# 8_dc_dc_5V_5A_Radio.net
KiCad netlist of a schematic drawn in Altium Designer
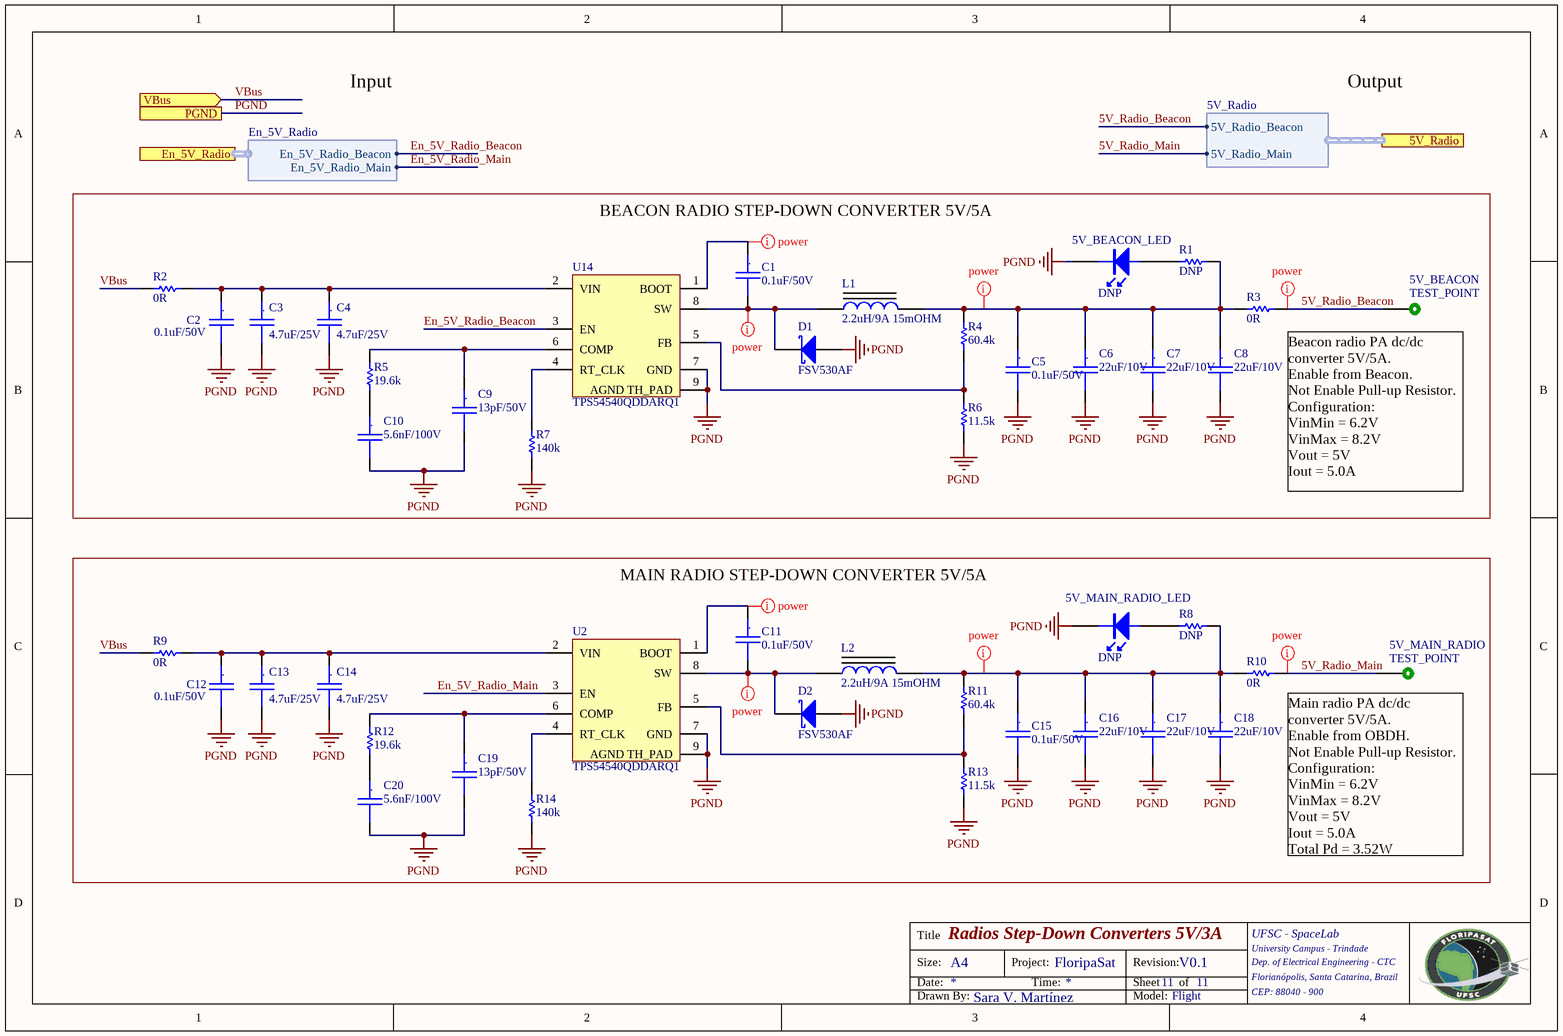
[diagram p0: 8_dc_dc_5V_5A_Radio.SchDoc]

(export (version "E")
  (design (tool "Eeschema 10.0.6"))
  (components
    (comp (ref "5V_BEACON")
      (value "TEST_POINT")
      (footprint "TEST_POINT")
      (description "Test point")
      (libsource (lib "Floripasat_lib") (part "TEST_POINT"))
    )
    (comp (ref "5V_BEACON_LED")
      (value "DNP")
      (footprint "0603-LED")
      (description "SMD Green LED")
      (fields (field (name "PARTNUMBER") "150060VS75000"))
      (libsource (lib "FloripaSatSchlib") (part "LED/G_0603"))
    )
    (comp (ref "5V_MAIN_RADIO")
      (value "TEST_POINT")
      (footprint "TEST_POINT")
      (description "Test point")
      (libsource (lib "Floripasat_lib") (part "TEST_POINT"))
    )
    (comp (ref "5V_MAIN_RADIO_LED")
      (value "DNP")
      (footprint "0603-LED")
      (description "SMD Green LED")
      (fields (field (name "PARTNUMBER") "150060VS75000"))
      (libsource (lib "FloripaSatSchlib") (part "LED/G_0603"))
    )
    (comp (ref "C1")
      (value "0.1uF/50V")
      (footprint "CC0805")
      (description "CAP CER 0.1UF 50V 10% X7R 0805")
      (fields (field (name "PARTNUMBER") "CC0805KRX7R9BB104"))
      (libsource (lib "PCB_Project_FlightModel_EPS") (part "Cap_Cer_X7R_0.1uF_50V_0805"))
    )
    (comp (ref "C2")
      (value "0.1uF/50V")
      (footprint "CC0805")
      (description "CAP CER 0.1UF 50V 10% X7R 0805")
      (fields (field (name "PARTNUMBER") "CC0805KRX7R9BB104"))
      (libsource (lib "PCB_Project_FlightModel_EPS") (part "Cap_Cer_X7R_0.1uF_50V_0805"))
    )
    (comp (ref "C3")
      (value "4.7uF/25V")
      (footprint "CC0805")
      (description "CAP CER 4.7uF 25V 10% X7R 0805")
      (fields (field (name "PARTNUMBER") "CC0805KKX7R8BB475"))
      (libsource (lib "PCB_Project_FlightModel_EPS") (part "Cap_Cer_X7R_4.7uF_25V_0805"))
    )
    (comp (ref "C4")
      (value "4.7uF/25V")
      (footprint "CC0805")
      (description "CAP CER 4.7uF 25V 10% X7R 0805")
      (fields (field (name "PARTNUMBER") "CC0805KKX7R8BB475"))
      (libsource (lib "PCB_Project_FlightModel_EPS") (part "Cap_Cer_X7R_4.7uF_25V_0805"))
    )
    (comp (ref "C5")
      (value "0.1uF/50V")
      (footprint "CC0805")
      (description "CAP CER 0.1UF 50V 10% X7R 0805")
      (fields (field (name "PARTNUMBER") "CC0805KRX7R9BB104"))
      (libsource (lib "PCB_Project_FlightModel_EPS") (part "Cap_Cer_X7R_0.1uF_50V_0805"))
    )
    (comp (ref "C6")
      (value "22uF/10V")
      (footprint "CC1206")
      (description "CAP CER 22uF 10V 10% X7R 1206")
      (fields (field (name "PARTNUMBER") "GRM31CR71A226KE15L"))
      (libsource (lib "PCB_Project_FlightModel_EPS") (part "Cap_Cer_X7R_22uF_10V_1206"))
    )
    (comp (ref "C7")
      (value "22uF/10V")
      (footprint "CC1206")
      (description "CAP CER 22uF 10V 10% X7R 1206")
      (fields (field (name "PARTNUMBER") "GRM31CR71A226KE15L"))
      (libsource (lib "PCB_Project_FlightModel_EPS") (part "Cap_Cer_X7R_22uF_10V_1206"))
    )
    (comp (ref "C8")
      (value "22uF/10V")
      (footprint "CC1206")
      (description "CAP CER 22uF 10V 10% X7R 1206")
      (fields (field (name "PARTNUMBER") "GRM31CR71A226KE15L"))
      (libsource (lib "PCB_Project_FlightModel_EPS") (part "Cap_Cer_X7R_22uF_10V_1206"))
    )
    (comp (ref "C9")
      (value "13pF/50V")
      (footprint "CC0603")
      (description "CAP CER 13PF 50V 0603 NP0")
      (fields (field (name "PARTNUMBER") "C0603C130J5GAC7867"))
      (libsource (lib "PCB_Project_FlightModel_EPS") (part "Cap_Cer_C0G_13pF_50V_0603"))
    )
    (comp (ref "C10")
      (value "5.6nF/100V")
      (footprint "CC0603")
      (description "CAP CER 5.6nF 100V 0603")
      (fields (field (name "PARTNUMBER") "C1608C0G2A562J080AE"))
      (libsource (lib "FloripaSatSchlib") (part "Cap_Cer_C0G_5.6nF_100V_0603"))
    )
    (comp (ref "C11")
      (value "0.1uF/50V")
      (footprint "CC0805")
      (description "CAP CER 0.1UF 50V 10% X7R 0805")
      (fields (field (name "PARTNUMBER") "CC0805KRX7R9BB104"))
      (libsource (lib "PCB_Project_FlightModel_EPS") (part "Cap_Cer_X7R_0.1uF_50V_0805"))
    )
    (comp (ref "C12")
      (value "0.1uF/50V")
      (footprint "CC0805")
      (description "CAP CER 0.1UF 50V 10% X7R 0805")
      (fields (field (name "PARTNUMBER") "CC0805KRX7R9BB104"))
      (libsource (lib "PCB_Project_FlightModel_EPS") (part "Cap_Cer_X7R_0.1uF_50V_0805"))
    )
    (comp (ref "C13")
      (value "4.7uF/25V")
      (footprint "CC0805")
      (description "CAP CER 4.7uF 25V 10% X7R 0805")
      (fields (field (name "PARTNUMBER") "CC0805KKX7R8BB475"))
      (libsource (lib "PCB_Project_FlightModel_EPS") (part "Cap_Cer_X7R_4.7uF_25V_0805"))
    )
    (comp (ref "C14")
      (value "4.7uF/25V")
      (footprint "CC0805")
      (description "CAP CER 4.7uF 25V 10% X7R 0805")
      (fields (field (name "PARTNUMBER") "CC0805KKX7R8BB475"))
      (libsource (lib "PCB_Project_FlightModel_EPS") (part "Cap_Cer_X7R_4.7uF_25V_0805"))
    )
    (comp (ref "C15")
      (value "0.1uF/50V")
      (footprint "CC0805")
      (description "CAP CER 0.1UF 50V 10% X7R 0805")
      (fields (field (name "PARTNUMBER") "CC0805KRX7R9BB104"))
      (libsource (lib "PCB_Project_FlightModel_EPS") (part "Cap_Cer_X7R_0.1uF_50V_0805"))
    )
    (comp (ref "C16")
      (value "22uF/10V")
      (footprint "CC1206")
      (description "CAP CER 22uF 10V 10% X7R 1206")
      (fields (field (name "PARTNUMBER") "GRM31CR71A226KE15L"))
      (libsource (lib "PCB_Project_FlightModel_EPS") (part "Cap_Cer_X7R_22uF_10V_1206"))
    )
    (comp (ref "C17")
      (value "22uF/10V")
      (footprint "CC1206")
      (description "CAP CER 22uF 10V 10% X7R 1206")
      (fields (field (name "PARTNUMBER") "GRM31CR71A226KE15L"))
      (libsource (lib "PCB_Project_FlightModel_EPS") (part "Cap_Cer_X7R_22uF_10V_1206"))
    )
    (comp (ref "C18")
      (value "22uF/10V")
      (footprint "CC1206")
      (description "CAP CER 22uF 10V 10% X7R 1206")
      (fields (field (name "PARTNUMBER") "GRM31CR71A226KE15L"))
      (libsource (lib "PCB_Project_FlightModel_EPS") (part "Cap_Cer_X7R_22uF_10V_1206"))
    )
    (comp (ref "C19")
      (value "13pF/50V")
      (footprint "CC0603")
      (description "CAP CER 13PF 50V 0603 NP0")
      (fields (field (name "PARTNUMBER") "C0603C130J5GAC7867"))
      (libsource (lib "PCB_Project_FlightModel_EPS") (part "Cap_Cer_C0G_13pF_50V_0603"))
    )
    (comp (ref "C20")
      (value "5.6nF/100V")
      (footprint "CC0603")
      (description "CAP CER 5.6nF 100V 0603")
      (fields (field (name "PARTNUMBER") "C1608C0G2A562J080AE"))
      (libsource (lib "FloripaSatSchlib") (part "Cap_Cer_C0G_5.6nF_100V_0603"))
    )
    (comp (ref "D1")
      (value "FSV530AF")
      (footprint "DO-214AC")
      (description "DIODE SCHOTTKY 30V 5A DO-214AA")
      (libsource (lib "FloripaSatSchlib") (part "DIODE_SCHOTTKY_30V_5A_RB080L-30TE25"))
    )
    (comp (ref "D2")
      (value "FSV530AF")
      (footprint "DO-214AC")
      (description "DIODE SCHOTTKY 30V 5A DO-214AA")
      (libsource (lib "FloripaSatSchlib") (part "DIODE_SCHOTTKY_30V_5A_RB080L-30TE25"))
    )
    (comp (ref "L1")
      (value "2.2uH/9A 15mOHM")
      (footprint "Ind_SRP6540")
      (description "INDUCTOR 2.2UH 9A SMD")
      (fields (field (name "PARTNUMBER") "SRP6540-2R2M"))
      (libsource (lib "FloripaSatSchlib") (part "IND_POWER_2.2uH_9A_15mR"))
    )
    (comp (ref "L2")
      (value "2.2uH/9A 15mOHM")
      (footprint "Ind_SRP6540")
      (description "INDUCTOR 2.2UH 9A SMD")
      (fields (field (name "PARTNUMBER") "SRP6540-2R2M"))
      (libsource (lib "FloripaSatSchlib") (part "IND_POWER_2.2uH_9A_15mR"))
    )
    (comp (ref "R1")
      (value "DNP")
      (footprint "0603")
      (description "RES 1.0K OHM 1/8W 1% 0603")
      (fields (field (name "PARTNUMBER") "MCT06030C1001FP500"))
      (libsource (lib "FloripaSatSchlib") (part "R1.0k_1%_1/8W_0603"))
    )
    (comp (ref "R2")
      (value "0R")
      (footprint "1206")
      (description "RES 0.0 OHM 3/4W JUMP 1206")
      (fields (field (name "PARTNUMBER") "HCJ1206ZT0R00"))
      (libsource (lib "PCB_Project_FlightModel_EPS") (part "R0R_JUMPER_3/4W_1206"))
    )
    (comp (ref "R3")
      (value "0R")
      (footprint "1206")
      (description "RES 0.0 OHM 3/4W JUMP 1206")
      (fields (field (name "PARTNUMBER") "HCJ1206ZT0R00"))
      (libsource (lib "PCB_Project_FlightModel_EPS") (part "R0R_JUMPER_3/4W_1206"))
    )
    (comp (ref "R4")
      (value "60.4k")
      (footprint "0805")
      (description "RES 60.4k OHM 1/8W 1% 0805")
      (fields (field (name "PARTNUMBER") "ERJ-6ENF6042V"))
      (libsource (lib "FloripaSatSchlib") (part "R60.4k_1%_1/8W_0805"))
    )
    (comp (ref "R5")
      (value "19.6k")
      (footprint "0603")
      (description "RES 19.6k OHM 1/10W 1% 0603")
      (fields (field (name "PARTNUMBER") "ERJ-3EKF1962V"))
      (libsource (lib "FloripaSatSchlib") (part "R19.6k_1%_1/10W_0603"))
    )
    (comp (ref "R6")
      (value "11.5k")
      (footprint "0805")
      (description "RES 11.5k OHM 1/8W 1% 0805")
      (fields (field (name "PARTNUMBER") "AC0805FR-0711K5L"))
      (libsource (lib "FloripaSatSchlib") (part "R11.5k_1%_1/8W_0805"))
    )
    (comp (ref "R7")
      (value "140k")
      (footprint "0603")
      (description "RES 140k OHM 1/5W 1% 0603")
      (fields (field (name "PARTNUMBER") "ERJ-P03F1403V"))
      (libsource (lib "FloripaSatSchlib") (part "R140k_1%_1/5W_0603"))
    )
    (comp (ref "R8")
      (value "DNP")
      (footprint "0603")
      (description "RES 1.0K OHM 1/8W 1% 0603")
      (fields (field (name "PARTNUMBER") "MCT06030C1001FP500"))
      (libsource (lib "FloripaSatSchlib") (part "R1.0k_1%_1/8W_0603"))
    )
    (comp (ref "R9")
      (value "0R")
      (footprint "1206")
      (description "RES 0.0 OHM 3/4W JUMP 1206")
      (fields (field (name "PARTNUMBER") "HCJ1206ZT0R00"))
      (libsource (lib "PCB_Project_FlightModel_EPS") (part "R0R_JUMPER_3/4W_1206"))
    )
    (comp (ref "R10")
      (value "0R")
      (footprint "1206")
      (description "RES 0.0 OHM 3/4W JUMP 1206")
      (fields (field (name "PARTNUMBER") "HCJ1206ZT0R00"))
      (libsource (lib "PCB_Project_FlightModel_EPS") (part "R0R_JUMPER_3/4W_1206"))
    )
    (comp (ref "R11")
      (value "60.4k")
      (footprint "0805")
      (description "RES 60.4k OHM 1/8W 1% 0805")
      (fields (field (name "PARTNUMBER") "ERJ-6ENF6042V"))
      (libsource (lib "FloripaSatSchlib") (part "R60.4k_1%_1/8W_0805"))
    )
    (comp (ref "R12")
      (value "19.6k")
      (footprint "0603")
      (description "RES 19.6k OHM 1/10W 1% 0603")
      (fields (field (name "PARTNUMBER") "ERJ-3EKF1962V"))
      (libsource (lib "FloripaSatSchlib") (part "R19.6k_1%_1/10W_0603"))
    )
    (comp (ref "R13")
      (value "11.5k")
      (footprint "0805")
      (description "RES 11.5k OHM 1/8W 1% 0805")
      (fields (field (name "PARTNUMBER") "AC0805FR-0711K5L"))
      (libsource (lib "FloripaSatSchlib") (part "R11.5k_1%_1/8W_0805"))
    )
    (comp (ref "R14")
      (value "140k")
      (footprint "0603")
      (description "RES 140k OHM 1/5W 1% 0603")
      (fields (field (name "PARTNUMBER") "ERJ-P03F1403V"))
      (libsource (lib "FloripaSatSchlib") (part "R140k_1%_1/5W_0603"))
    )
    (comp (ref "U2")
      (value "TPS54540QDDARQ1")
      (footprint "SO8 Power PAD")
      (libsource (lib "FloripaSatSchlib") (part "TPS54540QDDARQ1"))
    )
    (comp (ref "U14")
      (value "TPS54540QDDARQ1")
      (footprint "SO8 Power PAD")
      (libsource (lib "FloripaSatSchlib") (part "TPS54540QDDARQ1"))
    )
  )
  (nets
    (net (code "3") (name "/5V_Radio_Beacon") (class "Default")
      (node (ref "5V_BEACON") (pin "1") (pinfunction "1_1") (pintype "passive"))
      (node (ref "R3") (pin "1") (pinfunction "1_1") (pintype "passive"))
    )
    (net (code "4") (name "/5V_Radio_Main") (class "Default")
      (node (ref "5V_MAIN_RADIO") (pin "1") (pinfunction "1_1") (pintype "passive"))
      (node (ref "R10") (pin "1") (pinfunction "1_1") (pintype "passive"))
    )
    (net (code "5") (name "/En_5V_Radio_Beacon") (class "Default")
      (node (ref "U14") (pin "3") (pinfunction "EN_3") (pintype "passive"))
    )
    (net (code "6") (name "/En_5V_Radio_Main") (class "Default")
      (node (ref "U2") (pin "3") (pinfunction "EN_3") (pintype "passive"))
    )
    (net (code "7") (name "/VBus") (class "Default")
      (node (ref "R2") (pin "2") (pinfunction "2_2") (pintype "passive"))
      (node (ref "R9") (pin "2") (pinfunction "2_2") (pintype "passive"))
    )
    (net (code "10") (name "Net-(5V_BEACON_LED-A)") (class "Default")
      (node (ref "5V_BEACON_LED") (pin "1") (pinfunction "A_1") (pintype "passive"))
      (node (ref "R1") (pin "2") (pinfunction "2_2") (pintype "passive"))
    )
    (net (code "11") (name "Net-(5V_MAIN_RADIO_LED-A)") (class "Default")
      (node (ref "5V_MAIN_RADIO_LED") (pin "1") (pinfunction "A_1") (pintype "passive"))
      (node (ref "R8") (pin "2") (pinfunction "2_2") (pintype "passive"))
    )
    (net (code "12") (name "Net-(C5-Pad1)") (class "Default")
      (node (ref "C5") (pin "1") (pinfunction "1_1") (pintype "passive"))
      (node (ref "C6") (pin "1") (pinfunction "1_1") (pintype "passive"))
      (node (ref "C7") (pin "1") (pinfunction "1_1") (pintype "passive"))
      (node (ref "C8") (pin "1") (pinfunction "1_1") (pintype "passive"))
      (node (ref "L1") (pin "2") (pinfunction "2_2") (pintype "passive"))
      (node (ref "R1") (pin "1") (pinfunction "1_1") (pintype "passive"))
      (node (ref "R3") (pin "2") (pinfunction "2_2") (pintype "passive"))
      (node (ref "R4") (pin "2") (pinfunction "2_2") (pintype "passive"))
    )
    (net (code "13") (name "Net-(C10-Pad1)") (class "Default")
      (node (ref "C10") (pin "1") (pinfunction "1_1") (pintype "passive"))
      (node (ref "R5") (pin "1") (pinfunction "1_1") (pintype "passive"))
    )
    (net (code "14") (name "Net-(C15-Pad1)") (class "Default")
      (node (ref "C15") (pin "1") (pinfunction "1_1") (pintype "passive"))
      (node (ref "C16") (pin "1") (pinfunction "1_1") (pintype "passive"))
      (node (ref "C17") (pin "1") (pinfunction "1_1") (pintype "passive"))
      (node (ref "C18") (pin "1") (pinfunction "1_1") (pintype "passive"))
      (node (ref "L2") (pin "2") (pinfunction "2_2") (pintype "passive"))
      (node (ref "R10") (pin "2") (pinfunction "2_2") (pintype "passive"))
      (node (ref "R11") (pin "2") (pinfunction "2_2") (pintype "passive"))
      (node (ref "R8") (pin "1") (pinfunction "1_1") (pintype "passive"))
    )
    (net (code "15") (name "Net-(C20-Pad1)") (class "Default")
      (node (ref "C20") (pin "1") (pinfunction "1_1") (pintype "passive"))
      (node (ref "R12") (pin "1") (pinfunction "1_1") (pintype "passive"))
    )
    (net (code "16") (name "Net-(D1-K)") (class "Default")
      (node (ref "C1") (pin "2") (pinfunction "2_2") (pintype "passive"))
      (node (ref "D1") (pin "1") (pinfunction "K_1") (pintype "passive"))
      (node (ref "L1") (pin "1") (pinfunction "1_1") (pintype "passive"))
      (node (ref "U14") (pin "8") (pinfunction "SW_8") (pintype "passive"))
    )
    (net (code "17") (name "Net-(D2-K)") (class "Default")
      (node (ref "C11") (pin "2") (pinfunction "2_2") (pintype "passive"))
      (node (ref "D2") (pin "1") (pinfunction "K_1") (pintype "passive"))
      (node (ref "L2") (pin "1") (pinfunction "1_1") (pintype "passive"))
      (node (ref "U2") (pin "8") (pinfunction "SW_8") (pintype "passive"))
    )
    (net (code "18") (name "Net-(U2-BOOT)") (class "Default")
      (node (ref "C11") (pin "1") (pinfunction "1_1") (pintype "passive"))
      (node (ref "U2") (pin "1") (pinfunction "BOOT_1") (pintype "passive"))
    )
    (net (code "19") (name "Net-(U2-COMP)") (class "Default")
      (node (ref "C19") (pin "1") (pinfunction "1_1") (pintype "passive"))
      (node (ref "R12") (pin "2") (pinfunction "2_2") (pintype "passive"))
      (node (ref "U2") (pin "6") (pinfunction "COMP_6") (pintype "passive"))
    )
    (net (code "20") (name "Net-(U2-FB)") (class "Default")
      (node (ref "R11") (pin "1") (pinfunction "1_1") (pintype "passive"))
      (node (ref "R13") (pin "2") (pinfunction "2_2") (pintype "passive"))
      (node (ref "U2") (pin "5") (pinfunction "FB_5") (pintype "passive"))
    )
    (net (code "21") (name "Net-(U2-RT_CLK)") (class "Default")
      (node (ref "R14") (pin "2") (pinfunction "2_2") (pintype "passive"))
      (node (ref "U2") (pin "4") (pinfunction "RT_CLK_4") (pintype "passive"))
    )
    (net (code "22") (name "Net-(U2-VIN)") (class "Default")
      (node (ref "C12") (pin "1") (pinfunction "1_1") (pintype "passive"))
      (node (ref "C13") (pin "1") (pinfunction "1_1") (pintype "passive"))
      (node (ref "C14") (pin "1") (pinfunction "1_1") (pintype "passive"))
      (node (ref "R9") (pin "1") (pinfunction "1_1") (pintype "passive"))
      (node (ref "U2") (pin "2") (pinfunction "VIN_2") (pintype "passive"))
    )
    (net (code "23") (name "Net-(U14-BOOT)") (class "Default")
      (node (ref "C1") (pin "1") (pinfunction "1_1") (pintype "passive"))
      (node (ref "U14") (pin "1") (pinfunction "BOOT_1") (pintype "passive"))
    )
    (net (code "24") (name "Net-(U14-COMP)") (class "Default")
      (node (ref "C9") (pin "1") (pinfunction "1_1") (pintype "passive"))
      (node (ref "R5") (pin "2") (pinfunction "2_2") (pintype "passive"))
      (node (ref "U14") (pin "6") (pinfunction "COMP_6") (pintype "passive"))
    )
    (net (code "25") (name "Net-(U14-FB)") (class "Default")
      (node (ref "R4") (pin "1") (pinfunction "1_1") (pintype "passive"))
      (node (ref "R6") (pin "2") (pinfunction "2_2") (pintype "passive"))
      (node (ref "U14") (pin "5") (pinfunction "FB_5") (pintype "passive"))
    )
    (net (code "26") (name "Net-(U14-RT_CLK)") (class "Default")
      (node (ref "R7") (pin "2") (pinfunction "2_2") (pintype "passive"))
      (node (ref "U14") (pin "4") (pinfunction "RT_CLK_4") (pintype "passive"))
    )
    (net (code "27") (name "Net-(U14-VIN)") (class "Default")
      (node (ref "C2") (pin "1") (pinfunction "1_1") (pintype "passive"))
      (node (ref "C3") (pin "1") (pinfunction "1_1") (pintype "passive"))
      (node (ref "C4") (pin "1") (pinfunction "1_1") (pintype "passive"))
      (node (ref "R2") (pin "1") (pinfunction "1_1") (pintype "passive"))
      (node (ref "U14") (pin "2") (pinfunction "VIN_2") (pintype "passive"))
    )
    (net (code "28") (name "PGND") (class "Default")
      (node (ref "5V_BEACON_LED") (pin "2") (pinfunction "K_2") (pintype "passive"))
      (node (ref "5V_MAIN_RADIO_LED") (pin "2") (pinfunction "K_2") (pintype "passive"))
      (node (ref "C10") (pin "2") (pinfunction "2_2") (pintype "passive"))
      (node (ref "C12") (pin "2") (pinfunction "2_2") (pintype "passive"))
      (node (ref "C13") (pin "2") (pinfunction "2_2") (pintype "passive"))
      (node (ref "C14") (pin "2") (pinfunction "2_2") (pintype "passive"))
      (node (ref "C15") (pin "2") (pinfunction "2_2") (pintype "passive"))
      (node (ref "C16") (pin "2") (pinfunction "2_2") (pintype "passive"))
      (node (ref "C17") (pin "2") (pinfunction "2_2") (pintype "passive"))
      (node (ref "C18") (pin "2") (pinfunction "2_2") (pintype "passive"))
      (node (ref "C19") (pin "2") (pinfunction "2_2") (pintype "passive"))
      (node (ref "C2") (pin "2") (pinfunction "2_2") (pintype "passive"))
      (node (ref "C20") (pin "2") (pinfunction "2_2") (pintype "passive"))
      (node (ref "C3") (pin "2") (pinfunction "2_2") (pintype "passive"))
      (node (ref "C4") (pin "2") (pinfunction "2_2") (pintype "passive"))
      (node (ref "C5") (pin "2") (pinfunction "2_2") (pintype "passive"))
      (node (ref "C6") (pin "2") (pinfunction "2_2") (pintype "passive"))
      (node (ref "C7") (pin "2") (pinfunction "2_2") (pintype "passive"))
      (node (ref "C8") (pin "2") (pinfunction "2_2") (pintype "passive"))
      (node (ref "C9") (pin "2") (pinfunction "2_2") (pintype "passive"))
      (node (ref "D1") (pin "2") (pinfunction "A_2") (pintype "passive"))
      (node (ref "D2") (pin "2") (pinfunction "A_2") (pintype "passive"))
      (node (ref "R13") (pin "1") (pinfunction "1_1") (pintype "passive"))
      (node (ref "R14") (pin "1") (pinfunction "1_1") (pintype "passive"))
      (node (ref "R6") (pin "1") (pinfunction "1_1") (pintype "passive"))
      (node (ref "R7") (pin "1") (pinfunction "1_1") (pintype "passive"))
      (node (ref "U14") (pin "7") (pinfunction "GND_7") (pintype "passive"))
      (node (ref "U14") (pin "9") (pinfunction "AGND_TH_PAD_9") (pintype "passive"))
      (node (ref "U2") (pin "7") (pinfunction "GND_7") (pintype "passive"))
      (node (ref "U2") (pin "9") (pinfunction "AGND_TH_PAD_9") (pintype "passive"))
    )
  )
)
